# smart-pedal.net
KiCad netlist of a schematic drawn in EAGLE
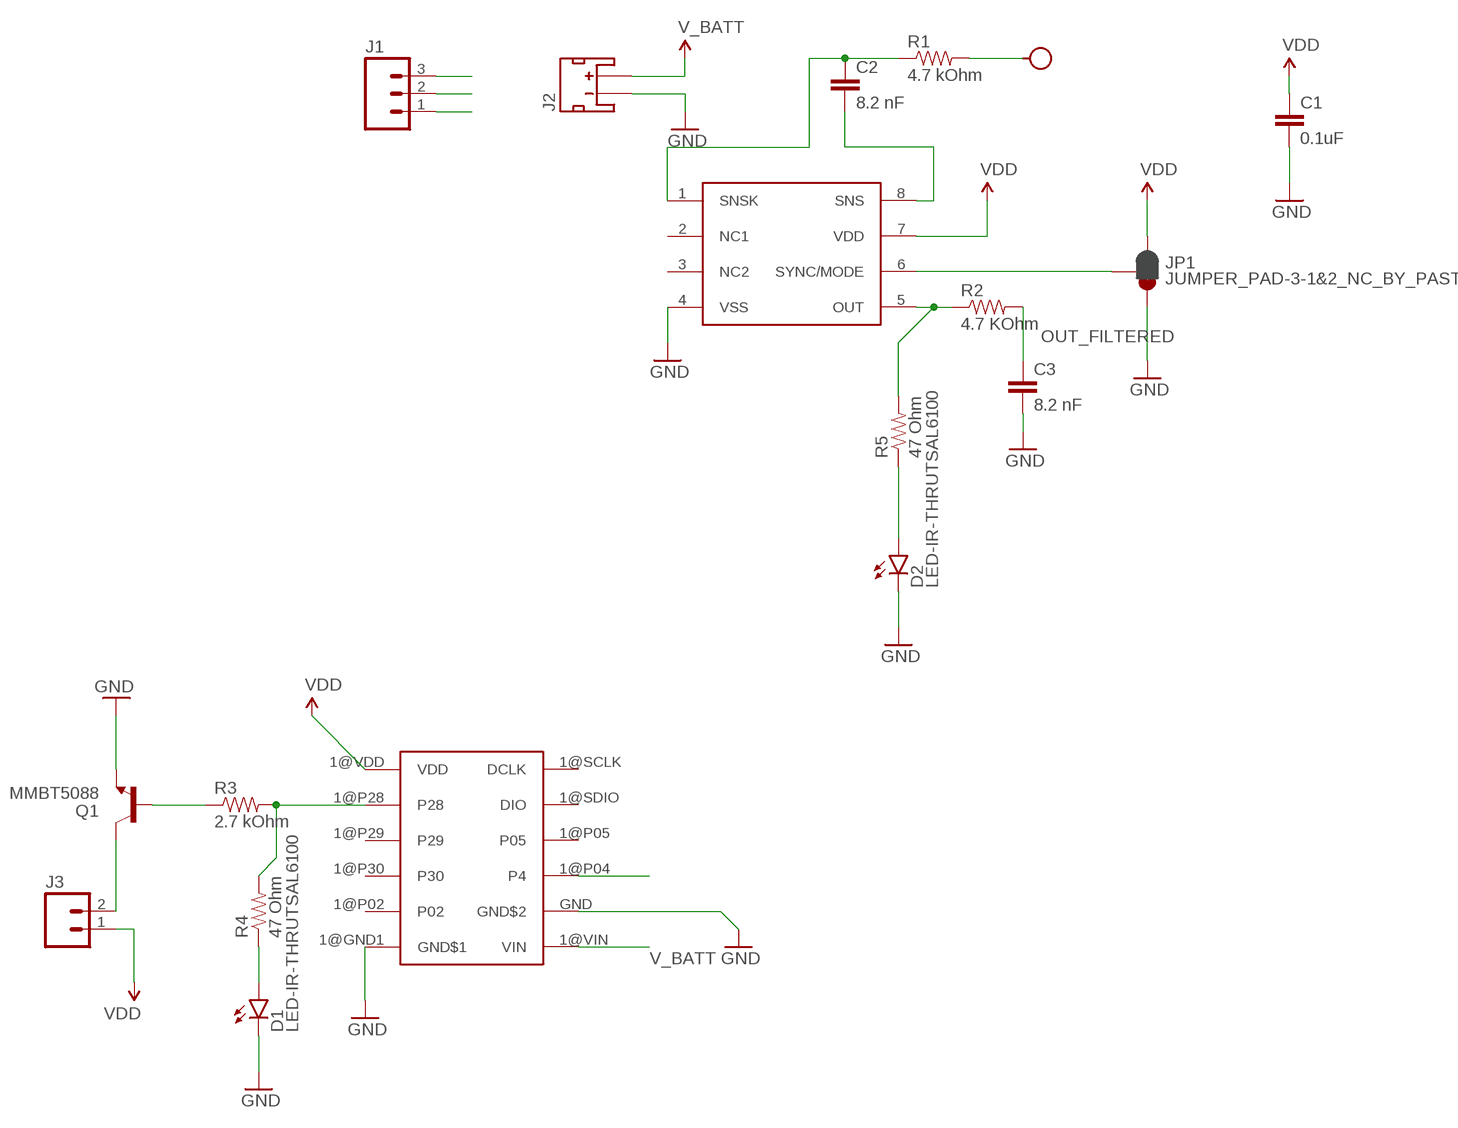
[diagram p0: schematic, sheet 1]

(export (version "E")
  (design (tool "Eeschema 10.0.6"))
  (components
    (comp (ref "C1")
      (value "0.1uF")
      (footprint "eagle-import:0603-CAP")
      (libsource (lib "eagle-import") (part "0.1UF-25V(+80/-20%)(0603)"))
    )
    (comp (ref "C2")
      (value "8.2 nF")
      (footprint "eagle-import:0603-CAP")
      (libsource (lib "eagle-import") (part "CAP0603-CAP"))
    )
    (comp (ref "C3")
      (value "8.2 nF")
      (footprint "eagle-import:0603-CAP")
      (libsource (lib "eagle-import") (part "CAP0603-CAP"))
    )
    (comp (ref "D1")
      (value "LED-IR-THRUTSAL6100")
      (footprint "eagle-import:LED5MM")
      (libsource (lib "eagle-import") (part "LED-IR-THRUTSAL6100"))
    )
    (comp (ref "D2")
      (value "LED-IR-THRUTSAL6100")
      (footprint "eagle-import:LED5MM")
      (libsource (lib "eagle-import") (part "LED-IR-THRUTSAL6100"))
    )
    (comp (ref "H1")
      (value "SEW_HOLE-SMALL")
      (footprint "eagle-import:SIMPLE_HOLE_SM")
      (libsource (lib "eagle-import") (part "SEW_HOLE-SMALL"))
    )
    (comp (ref "J1")
      (value "M03LOCK")
      (footprint "eagle-import:1X03_LOCK")
      (libsource (lib "eagle-import") (part "M03LOCK"))
    )
    (comp (ref "J2")
      (value "JST_2MM_MALE")
      (footprint "eagle-import:JST-2-SMD")
      (libsource (lib "eagle-import") (part "JST_2MM_MALE"))
    )
    (comp (ref "J3")
      (value "M02LOCK")
      (footprint "eagle-import:1X02_LOCK")
      (libsource (lib "eagle-import") (part "M02LOCK"))
    )
    (comp (ref "JP1")
      (value "JUMPER_PAD-3-1&2_NC_BY_PASTE")
      (footprint "eagle-import:PAD-HUMPER-3-1&2_NC_BY_PASTE_YES_SILK_FULL_BOX")
      (libsource (lib "eagle-import") (part "JUMPER_PAD-3-1&2_NC_BY_PASTE"))
    )
    (comp (ref "Q1")
      (value "MMBT5088")
      (footprint "eagle-import:SOT23-3")
      (libsource (lib "eagle-import") (part "TRANSISTOR_NPNMMBT5088"))
    )
    (comp (ref "R1")
      (value "4.7 kOhm")
      (footprint "eagle-import:0603-RES")
      (libsource (lib "eagle-import") (part "RESISTOR0603-RES"))
    )
    (comp (ref "R2")
      (value "4.7 KOhm")
      (footprint "eagle-import:0603-RES")
      (fields (field (name "SPICEPREFIX") "R"))
      (libsource (lib "eagle-import") (part "RESISTOR0603-RES"))
    )
    (comp (ref "R3")
      (value "2.7 kOhm")
      (footprint "eagle-import:0603-RES")
      (libsource (lib "eagle-import") (part "RESISTOR0603-RES"))
    )
    (comp (ref "R4")
      (value "47 Ohm")
      (footprint "eagle-import:0603-RES")
      (libsource (lib "eagle-import") (part "RESISTOR0603-RES"))
    )
    (comp (ref "R5")
      (value "47 Ohm")
      (footprint "eagle-import:0603-RES")
      (libsource (lib "eagle-import") (part "RESISTOR0603-RES"))
    )
    (comp (ref "U$1")
      (value "AT42QT1011")
      (footprint "eagle-import:UDFN8")
      (libsource (lib "eagle-import") (part "AT42QT1011"))
    )
    (comp (ref "U$2")
      (value "NANOV2")
      (footprint "eagle-import:NANOV2")
      (libsource (lib "eagle-import") (part "NANOV2"))
    )
  )
  (nets
    (net (code "1") (name "/MOTOR_OUT") (class "Default")
      (node (ref "J1") (pin "3") (pinfunction "3_3") (pintype "passive"))
      (node (ref "R3") (pin "2") (pinfunction "2_2") (pintype "passive"))
      (node (ref "R4") (pin "2") (pinfunction "2_2") (pintype "passive"))
      (node (ref "U$2") (pin "1@P28") (pinfunction "P28_1@P28") (pintype "bidirectional"))
    )
    (net (code "2") (name "/OUT_FILTERED") (class "Default")
      (node (ref "C3") (pin "1") (pinfunction "1_1") (pintype "passive"))
      (node (ref "J1") (pin "2") (pinfunction "2_2") (pintype "passive"))
      (node (ref "R2") (pin "2") (pinfunction "2_2") (pintype "passive"))
      (node (ref "U$2") (pin "1@P04") (pinfunction "P4_1@P04") (pintype "bidirectional"))
    )
    (net (code "3") (name "GND") (class "Default")
      (node (ref "C1") (pin "2") (pinfunction "2_2") (pintype "passive"))
      (node (ref "C3") (pin "2") (pinfunction "2_2") (pintype "passive"))
      (node (ref "D1") (pin "K") (pinfunction "C_K") (pintype "passive"))
      (node (ref "D2") (pin "K") (pinfunction "C_K") (pintype "passive"))
      (node (ref "J1") (pin "1") (pinfunction "1_1") (pintype "passive"))
      (node (ref "J2") (pin "1") (pinfunction "-_1") (pintype "bidirectional"))
      (node (ref "JP1") (pin "3") (pinfunction "3_3") (pintype "passive"))
      (node (ref "Q1") (pin "2") (pinfunction "E_2") (pintype "passive"))
      (node (ref "U$1") (pin "4") (pinfunction "VSS_4") (pintype "bidirectional"))
      (node (ref "U$2") (pin "1@GND1") (pinfunction "GND$1_1@GND1") (pintype "bidirectional"))
      (node (ref "U$2") (pin "GND") (pinfunction "GND$2_GND") (pintype "bidirectional"))
    )
    (net (code "4") (name "Net-(D1-PadA)") (class "Default")
      (node (ref "D1") (pin "A") (pinfunction "A_A") (pintype "passive"))
      (node (ref "R4") (pin "1") (pinfunction "1_1") (pintype "passive"))
    )
    (net (code "5") (name "Net-(D2-PadA)") (class "Default")
      (node (ref "D2") (pin "A") (pinfunction "A_A") (pintype "passive"))
      (node (ref "R5") (pin "1") (pinfunction "1_1") (pintype "passive"))
    )
    (net (code "6") (name "Net-(H1-PadP$1)") (class "Default")
      (node (ref "H1") (pin "P$1") (pinfunction "P$1_P$1") (pintype "bidirectional"))
      (node (ref "R1") (pin "2") (pinfunction "2_2") (pintype "passive"))
    )
    (net (code "7") (name "Net-(Q1-B)") (class "Default")
      (node (ref "Q1") (pin "1") (pinfunction "B_1") (pintype "passive"))
      (node (ref "R3") (pin "1") (pinfunction "1_1") (pintype "passive"))
    )
    (net (code "8") (name "Net-(Q1-C)") (class "Default")
      (node (ref "J3") (pin "2") (pinfunction "2_2") (pintype "passive"))
      (node (ref "Q1") (pin "3") (pinfunction "C_3") (pintype "passive"))
    )
    (net (code "9") (name "Net-(U$1-OUT)") (class "Default")
      (node (ref "R2") (pin "1") (pinfunction "1_1") (pintype "passive"))
      (node (ref "R5") (pin "2") (pinfunction "2_2") (pintype "passive"))
      (node (ref "U$1") (pin "5") (pinfunction "OUT_5") (pintype "bidirectional"))
    )
    (net (code "10") (name "Net-(U$1-SNS)") (class "Default")
      (node (ref "C2") (pin "2") (pinfunction "2_2") (pintype "passive"))
      (node (ref "U$1") (pin "8") (pinfunction "SNS_8") (pintype "bidirectional"))
    )
    (net (code "11") (name "Net-(U$1-SNSK)") (class "Default")
      (node (ref "C2") (pin "1") (pinfunction "1_1") (pintype "passive"))
      (node (ref "R1") (pin "1") (pinfunction "1_1") (pintype "passive"))
      (node (ref "U$1") (pin "1") (pinfunction "SNSK_1") (pintype "bidirectional"))
    )
    (net (code "12") (name "Net-(U$1-SYNC{slash}MODE)") (class "Default")
      (node (ref "JP1") (pin "2") (pinfunction "2_2") (pintype "passive"))
      (node (ref "U$1") (pin "6") (pinfunction "SYNC/MODE_6") (pintype "bidirectional"))
    )
    (net (code "13") (name "VDD") (class "Default")
      (node (ref "C1") (pin "1") (pinfunction "1_1") (pintype "passive"))
      (node (ref "J3") (pin "1") (pinfunction "1_1") (pintype "passive"))
      (node (ref "JP1") (pin "1") (pinfunction "1_1") (pintype "passive"))
      (node (ref "U$1") (pin "7") (pinfunction "VDD_7") (pintype "bidirectional"))
      (node (ref "U$2") (pin "1@VDD") (pinfunction "VDD_1@VDD") (pintype "bidirectional"))
    )
    (net (code "14") (name "V_BATT") (class "Default")
      (node (ref "J2") (pin "2") (pinfunction "+_2") (pintype "bidirectional"))
      (node (ref "U$2") (pin "1@VIN") (pinfunction "VIN_1@VIN") (pintype "bidirectional"))
    )
    (net (code "15") (name "unconnected-(J2-PAD1-PadNC1)") (class "Default")
      (node (ref "J2") (pin "NC1") (pinfunction "PAD1_NC1") (pintype "bidirectional"))
    )
    (net (code "16") (name "unconnected-(J2-PAD2-PadNC2)") (class "Default")
      (node (ref "J2") (pin "NC2") (pinfunction "PAD2_NC2") (pintype "bidirectional"))
    )
    (net (code "17") (name "unconnected-(U$1-NC1-Pad2)") (class "Default")
      (node (ref "U$1") (pin "2") (pinfunction "NC1_2") (pintype "bidirectional"))
    )
    (net (code "18") (name "unconnected-(U$1-NC2-Pad3)") (class "Default")
      (node (ref "U$1") (pin "3") (pinfunction "NC2_3") (pintype "bidirectional"))
    )
    (net (code "19") (name "unconnected-(U$2-DCLK-Pad1@SCLK)") (class "Default")
      (node (ref "U$2") (pin "1@SCLK") (pinfunction "DCLK_1@SCLK") (pintype "bidirectional"))
    )
    (net (code "20") (name "unconnected-(U$2-DIO-Pad1@SDIO)") (class "Default")
      (node (ref "U$2") (pin "1@SDIO") (pinfunction "DIO_1@SDIO") (pintype "bidirectional"))
    )
    (net (code "21") (name "unconnected-(U$2-P02-Pad1@P02)") (class "Default")
      (node (ref "U$2") (pin "1@P02") (pinfunction "P02_1@P02") (pintype "bidirectional"))
    )
    (net (code "22") (name "unconnected-(U$2-P05-Pad1@P05)") (class "Default")
      (node (ref "U$2") (pin "1@P05") (pinfunction "P05_1@P05") (pintype "bidirectional"))
    )
    (net (code "23") (name "unconnected-(U$2-P29-Pad1@P29)") (class "Default")
      (node (ref "U$2") (pin "1@P29") (pinfunction "P29_1@P29") (pintype "bidirectional"))
    )
    (net (code "24") (name "unconnected-(U$2-P30-Pad1@P30)") (class "Default")
      (node (ref "U$2") (pin "1@P30") (pinfunction "P30_1@P30") (pintype "bidirectional"))
    )
  )
)
